# esp32_v2.net
KiCad netlist of a schematic drawn in Altium Designer
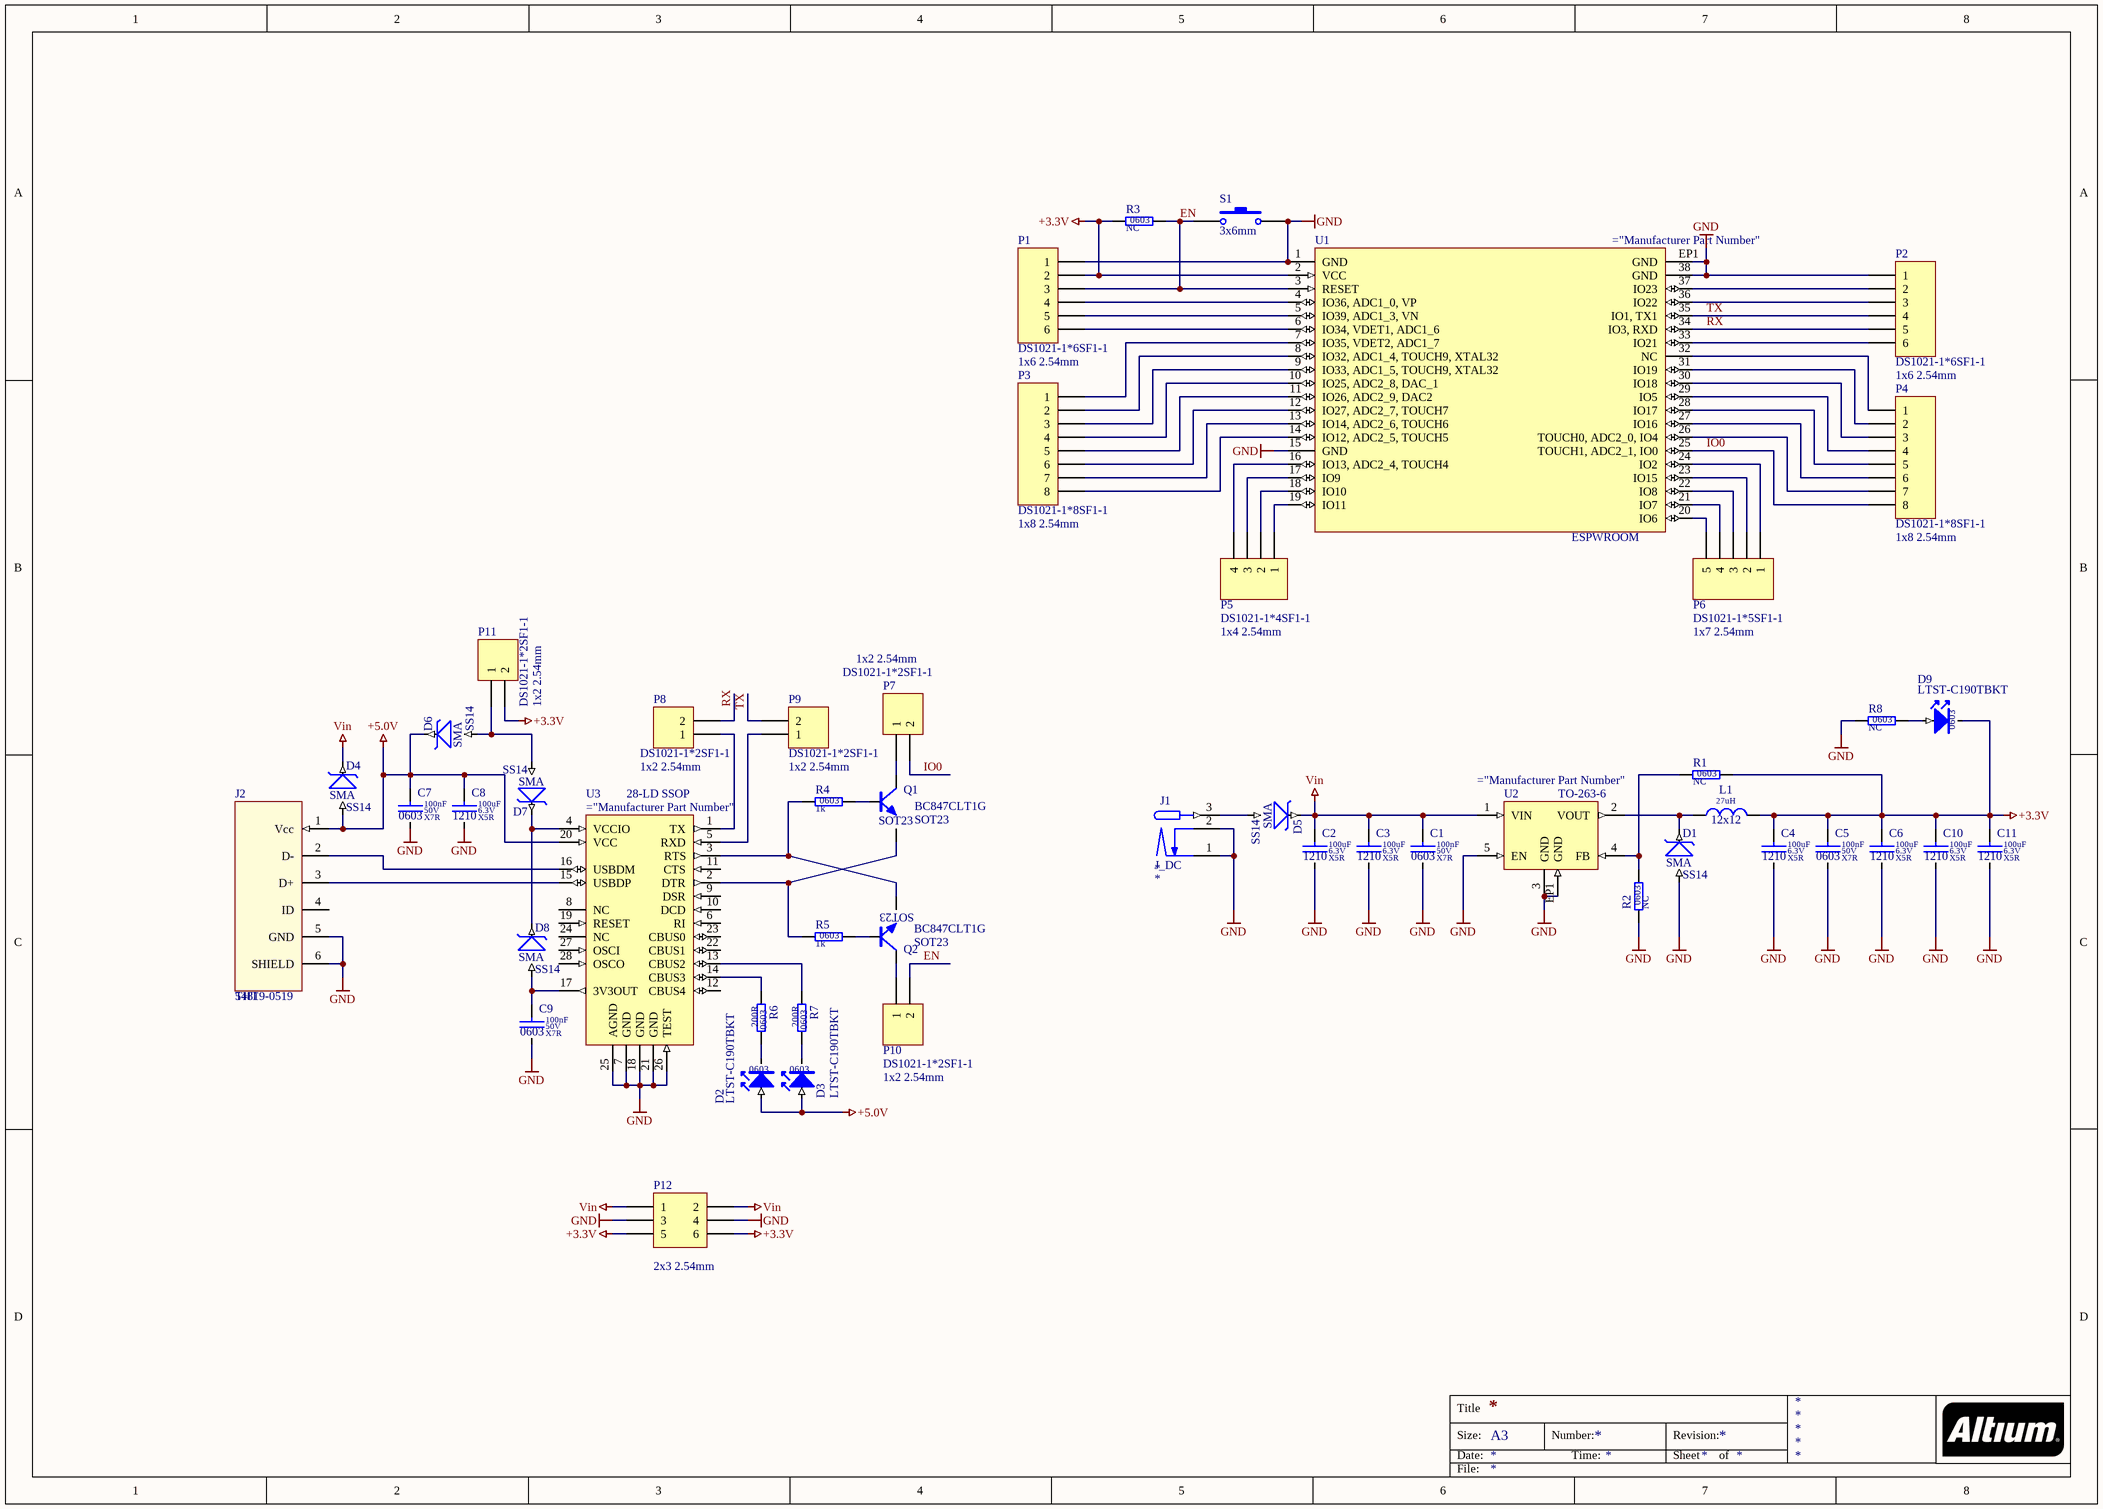
[diagram p0: esp32_v2.SchDoc]

(export (version "E")
  (design (tool "Eeschema 10.0.6"))
  (components
    (comp (ref "C1")
      (value "100nF")
      (footprint "C_0603_1608")
      (description "Capacitor")
      (fields
        (field (name "DIELECTRIC") "X7R")
        (field (name "VOLTAGE") "50V")
        (field (name "SCH_FOOTPRINT") "0603")
        (field (name "PART NUMBER") "C_100nF_50V_X7R_0603_5")
        (field (name "MANUFACTURER") "Samsung")
      )
      (libsource (lib "Library") (part "C"))
    )
    (comp (ref "C2")
      (value "100uF")
      (footprint "C_1210_3225")
      (description "Capacitor")
      (fields
        (field (name "DIELECTRIC") "X5R")
        (field (name "VOLTAGE") "6.3V")
        (field (name "SCH_FOOTPRINT") "1210")
        (field (name "PART NUMBER") "C_100uF_6.3V_X5R_1210_20")
        (field (name "MANUFACTURER") "TDK")
      )
      (libsource (lib "Library") (part "C"))
    )
    (comp (ref "C3")
      (value "100uF")
      (footprint "C_1210_3225")
      (description "Capacitor")
      (fields
        (field (name "DIELECTRIC") "X5R")
        (field (name "VOLTAGE") "6.3V")
        (field (name "SCH_FOOTPRINT") "1210")
        (field (name "PART NUMBER") "C_100uF_6.3V_X5R_1210_20")
        (field (name "MANUFACTURER") "TDK")
      )
      (libsource (lib "Library") (part "C"))
    )
    (comp (ref "C4")
      (value "100uF")
      (footprint "C_1210_3225")
      (description "Capacitor")
      (fields
        (field (name "DIELECTRIC") "X5R")
        (field (name "VOLTAGE") "6.3V")
        (field (name "SCH_FOOTPRINT") "1210")
        (field (name "PART NUMBER") "C_100uF_6.3V_X5R_1210_20")
        (field (name "MANUFACTURER") "TDK")
      )
      (libsource (lib "Library") (part "C"))
    )
    (comp (ref "C5")
      (value "100nF")
      (footprint "C_0603_1608")
      (description "Capacitor")
      (fields
        (field (name "DIELECTRIC") "X7R")
        (field (name "VOLTAGE") "50V")
        (field (name "SCH_FOOTPRINT") "0603")
        (field (name "PART NUMBER") "C_100nF_50V_X7R_0603_5")
        (field (name "MANUFACTURER") "Samsung")
      )
      (libsource (lib "Library") (part "C"))
    )
    (comp (ref "C6")
      (value "100uF")
      (footprint "C_1210_3225")
      (description "Capacitor")
      (fields
        (field (name "DIELECTRIC") "X5R")
        (field (name "VOLTAGE") "6.3V")
        (field (name "SCH_FOOTPRINT") "1210")
        (field (name "PART NUMBER") "C_100uF_6.3V_X5R_1210_20")
        (field (name "MANUFACTURER") "TDK")
      )
      (libsource (lib "Library") (part "C"))
    )
    (comp (ref "C7")
      (value "100nF")
      (footprint "C_0603_1608")
      (description "Capacitor")
      (fields
        (field (name "DIELECTRIC") "X7R")
        (field (name "VOLTAGE") "50V")
        (field (name "SCH_FOOTPRINT") "0603")
        (field (name "PART NUMBER") "C_100nF_50V_X7R_0603_5")
        (field (name "MANUFACTURER") "Samsung")
      )
      (libsource (lib "Library") (part "C"))
    )
    (comp (ref "C8")
      (value "100uF")
      (footprint "C_1210_3225")
      (description "Capacitor")
      (fields
        (field (name "DIELECTRIC") "X5R")
        (field (name "VOLTAGE") "6.3V")
        (field (name "SCH_FOOTPRINT") "1210")
        (field (name "PART NUMBER") "C_100uF_6.3V_X5R_1210_20")
        (field (name "MANUFACTURER") "TDK")
      )
      (libsource (lib "Library") (part "C"))
    )
    (comp (ref "C9")
      (value "100nF")
      (footprint "C_0603_1608")
      (description "Capacitor")
      (fields
        (field (name "DIELECTRIC") "X7R")
        (field (name "VOLTAGE") "50V")
        (field (name "SCH_FOOTPRINT") "0603")
        (field (name "PART NUMBER") "C_100nF_50V_X7R_0603_5")
        (field (name "MANUFACTURER") "Samsung")
      )
      (libsource (lib "Library") (part "C"))
    )
    (comp (ref "C10")
      (value "100uF")
      (footprint "C_1210_3225")
      (description "Capacitor")
      (fields
        (field (name "DIELECTRIC") "X5R")
        (field (name "VOLTAGE") "6.3V")
        (field (name "SCH_FOOTPRINT") "1210")
        (field (name "PART NUMBER") "C_100uF_6.3V_X5R_1210_20")
        (field (name "MANUFACTURER") "TDK")
      )
      (libsource (lib "Library") (part "C"))
    )
    (comp (ref "C11")
      (value "100uF")
      (footprint "C_1210_3225")
      (description "Capacitor")
      (fields
        (field (name "DIELECTRIC") "X5R")
        (field (name "VOLTAGE") "6.3V")
        (field (name "SCH_FOOTPRINT") "1210")
        (field (name "PART NUMBER") "C_100uF_6.3V_X5R_1210_20")
        (field (name "MANUFACTURER") "TDK")
      )
      (libsource (lib "Library") (part "C"))
    )
    (comp (ref "D1")
      (value "SS14")
      (footprint "SMA_DO-214AC")
      (fields
        (field (name "SCH_FOOTPRINT") "SMA")
        (field (name "PART NUMBER") "DS_SS14_1A_40V_SMA")
        (field (name "VOLTAGE") "40V")
        (field (name "MANUFACTURER") "Fairchild Semiconductor")
      )
      (libsource (lib "Library") (part "DS"))
    )
    (comp (ref "D2")
      (value "LTST-C190TBKT")
      (footprint "OL_0603_1608")
      (description "LED_BLUE")
      (fields
        (field (name "SCH_FOOTPRINT") "0603")
        (field (name "PART NUMBER") "OL_B_0603")
        (field (name "MANUFACTURER") "Lite-On")
      )
      (libsource (lib "Library") (part "OL_B"))
    )
    (comp (ref "D3")
      (value "LTST-C190TBKT")
      (footprint "OL_0603_1608")
      (description "LED_BLUE")
      (fields
        (field (name "SCH_FOOTPRINT") "0603")
        (field (name "PART NUMBER") "OL_B_0603")
        (field (name "MANUFACTURER") "Lite-On")
      )
      (libsource (lib "Library") (part "OL_B"))
    )
    (comp (ref "D4")
      (value "SS14")
      (footprint "SMA_DO-214AC")
      (fields
        (field (name "SCH_FOOTPRINT") "SMA")
        (field (name "PART NUMBER") "DS_SS14_1A_40V_SMA")
        (field (name "VOLTAGE") "40V")
        (field (name "MANUFACTURER") "Fairchild Semiconductor")
      )
      (libsource (lib "Library") (part "DS"))
    )
    (comp (ref "D5")
      (value "SS14")
      (footprint "SMA_DO-214AC")
      (fields
        (field (name "SCH_FOOTPRINT") "SMA")
        (field (name "PART NUMBER") "DS_SS14_1A_40V_SMA")
        (field (name "VOLTAGE") "40V")
        (field (name "MANUFACTURER") "Fairchild Semiconductor")
      )
      (libsource (lib "Library") (part "DS"))
    )
    (comp (ref "D6")
      (value "SS14")
      (footprint "SMA_DO-214AC")
      (fields
        (field (name "SCH_FOOTPRINT") "SMA")
        (field (name "PART NUMBER") "DS_SS14_1A_40V_SMA")
        (field (name "VOLTAGE") "40V")
        (field (name "MANUFACTURER") "Fairchild Semiconductor")
      )
      (libsource (lib "Library") (part "DS"))
    )
    (comp (ref "D7")
      (value "SS14")
      (footprint "SMA_DO-214AC")
      (fields
        (field (name "SCH_FOOTPRINT") "SMA")
        (field (name "PART NUMBER") "DS_SS14_1A_40V_SMA")
        (field (name "VOLTAGE") "40V")
        (field (name "MANUFACTURER") "Fairchild Semiconductor")
      )
      (libsource (lib "Library") (part "DS"))
    )
    (comp (ref "D8")
      (value "SS14")
      (footprint "SMA_DO-214AC")
      (fields
        (field (name "SCH_FOOTPRINT") "SMA")
        (field (name "PART NUMBER") "DS_SS14_1A_40V_SMA")
        (field (name "VOLTAGE") "40V")
        (field (name "MANUFACTURER") "Fairchild Semiconductor")
      )
      (libsource (lib "Library") (part "DS"))
    )
    (comp (ref "D9")
      (value "LTST-C190TBKT")
      (footprint "OL_0603_1608")
      (description "LED_BLUE")
      (fields
        (field (name "SCH_FOOTPRINT") "0603")
        (field (name "PART NUMBER") "OL_B_0603")
        (field (name "MANUFACTURER") "Lite-On")
      )
      (libsource (lib "Library") (part "OL_B"))
    )
    (comp (ref "J1")
      (value "J_DC")
      (footprint "DC_5.5")
      (fields
        (field (name "ALTIUM_VALUE") "*")
        (field (name "SCH_FOOTPRINT") "*")
        (field (name "PART NUMBER") "J_DC_5.5mm")
      )
      (libsource (lib "Lib") (part "J_DC"))
    )
    (comp (ref "J2")
      (value "54819-0519")
      (footprint "J_USB_MINIB_54819-0519_THT")
      (description "Złącze USB, Mini USB typu B, USB 2.0 OTG, Montaż przewlekany")
      (fields
        (field (name "PART NUMBER") "J_USB_MINIB_54819-0519")
        (field (name "SCH_FOOTPRINT") "THT")
        (field (name "MANUFACTURER") "Molex")
      )
      (libsource (lib "Library") (part "J_USB_MINIB_54819-0519_THT"))
    )
    (comp (ref "L1")
      (value "27uH")
      (footprint "L_SRR1280-XXXY")
      (description "Induction")
      (fields
        (field (name "SCH_FOOTPRINT") "12x12")
        (field (name "PART NUMBER") "L_27uH_3.9A_SRR1280")
        (field (name "MANUFACTURER") "Bourns")
      )
      (libsource (lib "Library") (part "L"))
    )
    (comp (ref "P1")
      (value "DS1021-1*6SF1-1")
      (footprint "P_HEADER_1x6_2.54")
      (description "Header, 6-Pin")
      (fields
        (field (name "PART NUMBER") "P_HEADER_1x6_2.54")
        (field (name "SCH_FOOTPRINT") "1x6 2.54mm")
        (field (name "MANUFACTURER") "Connfly")
      )
      (libsource (lib "Library") (part "P_HEADER_1x6"))
    )
    (comp (ref "P2")
      (value "DS1021-1*6SF1-1")
      (footprint "P_HEADER_1x6_2.54")
      (description "Header, 6-Pin")
      (fields
        (field (name "PART NUMBER") "P_HEADER_1x6_2.54")
        (field (name "SCH_FOOTPRINT") "1x6 2.54mm")
        (field (name "MANUFACTURER") "Connfly")
      )
      (libsource (lib "") (part "P_HEADER_1x6_1"))
    )
    (comp (ref "P3")
      (value "DS1021-1*8SF1-1")
      (footprint "P_HEADER_1x8_2.54")
      (description "Header, 8-Pin")
      (fields
        (field (name "PART NUMBER") "P_HEADER_1x8_2.54")
        (field (name "SCH_FOOTPRINT") "1x8 2.54mm")
        (field (name "MANUFACTURER") "Connfly")
      )
      (libsource (lib "Library") (part "P_HEADER_1x8"))
    )
    (comp (ref "P4")
      (value "DS1021-1*8SF1-1")
      (footprint "P_HEADER_1x8_2.54")
      (description "Header, 8-Pin")
      (fields
        (field (name "PART NUMBER") "P_HEADER_1x8_2.54")
        (field (name "SCH_FOOTPRINT") "1x8 2.54mm")
        (field (name "MANUFACTURER") "Connfly")
      )
      (libsource (lib "") (part "P_HEADER_1x8_1"))
    )
    (comp (ref "P5")
      (value "DS1021-1*4SF1-1")
      (footprint "P_HEADER_1x4_2.54")
      (description "Header, 4-Pin")
      (fields
        (field (name "PART NUMBER") "P_HEADER_1x4_2.54")
        (field (name "SCH_FOOTPRINT") "1x4 2.54mm")
        (field (name "MANUFACTURER") "Connfly")
      )
      (libsource (lib "Library") (part "P_HEADER_1x4"))
    )
    (comp (ref "P6")
      (value "DS1021-1*5SF1-1")
      (footprint "P_HEADER_1x5_2.54")
      (description "Header, 5-Pin")
      (fields
        (field (name "PART NUMBER") "P_HEADER_1x5_2.54")
        (field (name "SCH_FOOTPRINT") "1x7 2.54mm")
        (field (name "MANUFACTURER") "Connfly")
      )
      (libsource (lib "Library") (part "P_HEADER_1x5"))
    )
    (comp (ref "P7")
      (value "DS1021-1*2SF1-1")
      (footprint "P_HEADER_1x2_2.54")
      (description "Header, 2-Pin")
      (fields
        (field (name "PART NUMBER") "P_HEADER_1x2_2.54")
        (field (name "SCH_FOOTPRINT") "1x2 2.54mm")
        (field (name "MANUFACTURER") "Connfly")
      )
      (libsource (lib "") (part "P_HEADER_1x2_1"))
    )
    (comp (ref "P8")
      (value "DS1021-1*2SF1-1")
      (footprint "P_HEADER_1x2_2.54")
      (description "Header, 2-Pin")
      (fields
        (field (name "PART NUMBER") "P_HEADER_1x2_2.54")
        (field (name "SCH_FOOTPRINT") "1x2 2.54mm")
        (field (name "MANUFACTURER") "Connfly")
      )
      (libsource (lib "Library") (part "P_HEADER_1x2"))
    )
    (comp (ref "P9")
      (value "DS1021-1*2SF1-1")
      (footprint "P_HEADER_1x2_2.54")
      (description "Header, 2-Pin")
      (fields
        (field (name "PART NUMBER") "P_HEADER_1x2_2.54")
        (field (name "SCH_FOOTPRINT") "1x2 2.54mm")
        (field (name "MANUFACTURER") "Connfly")
      )
      (libsource (lib "") (part "P_HEADER_1x2_1"))
    )
    (comp (ref "P10")
      (value "DS1021-1*2SF1-1")
      (footprint "P_HEADER_1x2_2.54")
      (description "Header, 2-Pin")
      (fields
        (field (name "PART NUMBER") "P_HEADER_1x2_2.54")
        (field (name "SCH_FOOTPRINT") "1x2 2.54mm")
        (field (name "MANUFACTURER") "Connfly")
      )
      (libsource (lib "Library") (part "P_HEADER_1x2"))
    )
    (comp (ref "P11")
      (value "DS1021-1*2SF1-1")
      (footprint "P_HEADER_1x2_2.54")
      (description "Header, 2-Pin")
      (fields
        (field (name "PART NUMBER") "P_HEADER_1x2_2.54")
        (field (name "SCH_FOOTPRINT") "1x2 2.54mm")
        (field (name "MANUFACTURER") "Connfly")
      )
      (libsource (lib "") (part "P_HEADER_1x2_1"))
    )
    (comp (ref "P12")
      (value "Goldpin")
      (footprint "P_HEADER_2x3_2.54")
      (description "Header, 3-Pin, Dual row")
      (fields (field (name "PART NUMBER") "P_HEADER_2x3_2.54") (field (name "SCH_FOOTPRINT") "2x3 2.54mm"))
      (libsource (lib "Library") (part "P_HEADER_2x3"))
    )
    (comp (ref "Q1")
      (value "BC847CLT1G")
      (footprint "SOT23_TO236_SC59")
      (fields
        (field (name "PART NUMBER") "QNP_BC847C_45V_0A1")
        (field (name "SCH_FOOTPRINT") "SOT23")
        (field (name "VOLTAGE") "45V")
        (field (name "MANUFACTURER") "ON Semiconductor")
      )
      (libsource (lib "Library") (part "QNP_BEC"))
    )
    (comp (ref "Q2")
      (value "BC847CLT1G")
      (footprint "SOT23_TO236_SC59")
      (fields
        (field (name "PART NUMBER") "QNP_BC847C_45V_0A1")
        (field (name "SCH_FOOTPRINT") "SOT23")
        (field (name "VOLTAGE") "45V")
        (field (name "MANUFACTURER") "ON Semiconductor")
      )
      (libsource (lib "Library") (part "QNP_BEC"))
    )
    (comp (ref "R1")
      (value "NC")
      (footprint "R_NC_0603_1608")
      (fields
        (field (name "SCH_FOOTPRINT") "0603")
        (field (name "PART NUMBER") "R_GENERIC_0603")
        (field (name "Comment") "Resistor")
      )
      (libsource (lib "Library") (part "R"))
    )
    (comp (ref "R2")
      (value "NC")
      (footprint "R_NC_0603_1608")
      (fields
        (field (name "SCH_FOOTPRINT") "0603")
        (field (name "PART NUMBER") "R_GENERIC_0603")
        (field (name "Comment") "Resistor")
      )
      (libsource (lib "Library") (part "R"))
    )
    (comp (ref "R3")
      (value "NC")
      (footprint "R_NC_0603_1608")
      (fields
        (field (name "SCH_FOOTPRINT") "0603")
        (field (name "PART NUMBER") "R_GENERIC_0603")
        (field (name "Comment") "Resistor")
      )
      (libsource (lib "Library") (part "R"))
    )
    (comp (ref "R4")
      (value "1k")
      (footprint "R_0603_1608")
      (fields
        (field (name "SCH_FOOTPRINT") "0603")
        (field (name "PART NUMBER") "R_1k_0603_1")
        (field (name "VOLTAGE") "75V")
        (field (name "POWER") "100mW")
      )
      (libsource (lib "Library") (part "R"))
    )
    (comp (ref "R5")
      (value "1k")
      (footprint "R_0603_1608")
      (fields
        (field (name "SCH_FOOTPRINT") "0603")
        (field (name "PART NUMBER") "R_1k_0603_1")
        (field (name "VOLTAGE") "75V")
        (field (name "POWER") "100mW")
      )
      (libsource (lib "Library") (part "R"))
    )
    (comp (ref "R6")
      (value "200R")
      (footprint "R_0603_1608")
      (fields
        (field (name "SCH_FOOTPRINT") "0603")
        (field (name "PART NUMBER") "R_200R_0603_1")
        (field (name "VOLTAGE") "50V")
        (field (name "POWER") "100mW")
      )
      (libsource (lib "Library") (part "R"))
    )
    (comp (ref "R7")
      (value "200R")
      (footprint "R_0603_1608")
      (fields
        (field (name "SCH_FOOTPRINT") "0603")
        (field (name "PART NUMBER") "R_200R_0603_1")
        (field (name "VOLTAGE") "50V")
        (field (name "POWER") "100mW")
      )
      (libsource (lib "Library") (part "R"))
    )
    (comp (ref "R8")
      (value "NC")
      (footprint "R_NC_0603_1608")
      (fields
        (field (name "SCH_FOOTPRINT") "0603")
        (field (name "PART NUMBER") "R_GENERIC_0603")
        (field (name "Comment") "Resistor")
      )
      (libsource (lib "Library") (part "R"))
    )
    (comp (ref "S1")
      (value "3x6mm")
      (footprint "S_TACTSWITCH3x6")
      (description "Tact Switch")
      (fields
        (field (name "PART NUMBER") "S_TACTSWITCH")
        (field (name "SCH_FOOTPRINT") "3x6mm")
        (field (name "MANUFACTURER") "Ninigi")
      )
      (libsource (lib "Library") (part "S_TACTSWITCH"))
    )
    (comp (ref "U1")
      (value "U_ESP32")
      (footprint "ESP_WROOM_32")
      (fields (field (name "SCH_FOOTPRINT") "ESPWROOM") (field (name "PART NUMBER") "M_ESP32_WROOM"))
      (libsource (lib "Lib") (part "U_ESP32"))
    )
    (comp (ref "U2")
      (value "VR_LM2596")
      (footprint "TO-263-6")
      (fields (field (name "SCH_FOOTPRINT") "TO-263-6") (field (name "PART NUMBER") "VR_LM2596-ADJ"))
      (libsource (lib "Lib") (part "VR_LM2596"))
    )
    (comp (ref "U3")
      (value "U_FT232RL")
      (footprint "SSOP28_5X10X17")
      (fields (field (name "SCH_FOOTPRINT") "28-LD SSOP") (field (name "PART NUMBER") "U_FT232RLR"))
      (libsource (lib "Lib") (part "U_FT232RL"))
    )
  )
  (nets
    (net (code "1") (name "+3.3V") (class "Default")
      (node (ref "C10") (pin "1") (pinfunction "1_1") (pintype "passive"))
      (node (ref "C11") (pin "1") (pinfunction "1_1") (pintype "passive"))
      (node (ref "C4") (pin "1") (pinfunction "1_1") (pintype "passive"))
      (node (ref "C5") (pin "1") (pinfunction "1_1") (pintype "passive"))
      (node (ref "C6") (pin "1") (pinfunction "1_1") (pintype "passive"))
      (node (ref "D9") (pin "1") (pinfunction "K_1") (pintype "output"))
      (node (ref "L1") (pin "2") (pinfunction "2_2") (pintype "passive"))
      (node (ref "P1") (pin "2") (pinfunction "2_2") (pintype "passive"))
      (node (ref "P11") (pin "2") (pinfunction "2_2") (pintype "passive"))
      (node (ref "P12") (pin "5") (pinfunction "5_5") (pintype "passive"))
      (node (ref "P12") (pin "6") (pinfunction "6_6") (pintype "passive"))
      (node (ref "R1") (pin "2") (pinfunction "2_2") (pintype "passive"))
      (node (ref "R3") (pin "1") (pinfunction "1_1") (pintype "passive"))
      (node (ref "U1") (pin "2") (pinfunction "VCC_2") (pintype "input"))
    )
    (net (code "2") (name "+5.0V") (class "Default")
      (node (ref "C7") (pin "1") (pinfunction "1_1") (pintype "passive"))
      (node (ref "C8") (pin "1") (pinfunction "1_1") (pintype "passive"))
      (node (ref "D2") (pin "2") (pinfunction "A_2") (pintype "input"))
      (node (ref "D3") (pin "2") (pinfunction "A_2") (pintype "input"))
      (node (ref "D4") (pin "2") (pintype "input"))
      (node (ref "D6") (pin "1") (pintype "output"))
      (node (ref "J2") (pin "1") (pinfunction "Vcc_1") (pintype "input"))
      (node (ref "U3") (pin "20") (pinfunction "VCC_20") (pintype "input"))
    )
    (net (code "3") (name "/EN") (class "Default")
      (node (ref "P1") (pin "3") (pinfunction "3_3") (pintype "passive"))
      (node (ref "P10") (pin "2") (pinfunction "2_2") (pintype "passive"))
      (node (ref "R3") (pin "2") (pinfunction "2_2") (pintype "passive"))
      (node (ref "S1") (pin "1") (pinfunction "1_1") (pintype "passive"))
      (node (ref "U1") (pin "3") (pinfunction "RESET_3") (pintype "input"))
    )
    (net (code "4") (name "/IO0") (class "Default")
      (node (ref "P4") (pin "8") (pinfunction "8_8") (pintype "passive"))
      (node (ref "P7") (pin "2") (pinfunction "2_2") (pintype "passive"))
      (node (ref "U1") (pin "25") (pinfunction "TOUCH1,_ADC2_1,_IO0_25") (pintype "bidirectional"))
    )
    (net (code "5") (name "/RX") (class "Default")
      (node (ref "P2") (pin "5") (pinfunction "5_5") (pintype "passive"))
      (node (ref "P8") (pin "2") (pinfunction "2_2") (pintype "passive"))
      (node (ref "U1") (pin "34") (pinfunction "IO3,_RXD_34") (pintype "bidirectional"))
    )
    (net (code "6") (name "/TX") (class "Default")
      (node (ref "P2") (pin "4") (pinfunction "4_4") (pintype "passive"))
      (node (ref "P9") (pin "2") (pinfunction "2_2") (pintype "passive"))
      (node (ref "U1") (pin "35") (pinfunction "IO1,_TX1_35") (pintype "bidirectional"))
    )
    (net (code "7") (name "GND") (class "Default")
      (node (ref "C1") (pin "2") (pinfunction "2_2") (pintype "passive"))
      (node (ref "C10") (pin "2") (pinfunction "2_2") (pintype "passive"))
      (node (ref "C11") (pin "2") (pinfunction "2_2") (pintype "passive"))
      (node (ref "C2") (pin "2") (pinfunction "2_2") (pintype "passive"))
      (node (ref "C3") (pin "2") (pinfunction "2_2") (pintype "passive"))
      (node (ref "C4") (pin "2") (pinfunction "2_2") (pintype "passive"))
      (node (ref "C5") (pin "2") (pinfunction "2_2") (pintype "passive"))
      (node (ref "C6") (pin "2") (pinfunction "2_2") (pintype "passive"))
      (node (ref "C7") (pin "2") (pinfunction "2_2") (pintype "passive"))
      (node (ref "C8") (pin "2") (pinfunction "2_2") (pintype "passive"))
      (node (ref "C9") (pin "2") (pinfunction "2_2") (pintype "passive"))
      (node (ref "D1") (pin "2") (pintype "input"))
      (node (ref "J1") (pin "1") (pinfunction "1_1") (pintype "power_in"))
      (node (ref "J1") (pin "2") (pinfunction "2_2") (pintype "passive"))
      (node (ref "J2") (pin "5") (pinfunction "GND_5") (pintype "power_in"))
      (node (ref "J2") (pin "6") (pinfunction "SHIELD_6") (pintype "passive"))
      (node (ref "P1") (pin "1") (pinfunction "1_1") (pintype "passive"))
      (node (ref "P12") (pin "3") (pinfunction "3_3") (pintype "passive"))
      (node (ref "P12") (pin "4") (pinfunction "4_4") (pintype "passive"))
      (node (ref "P2") (pin "1") (pinfunction "1_1") (pintype "passive"))
      (node (ref "R2") (pin "1") (pinfunction "1_1") (pintype "passive"))
      (node (ref "R8") (pin "1") (pinfunction "1_1") (pintype "passive"))
      (node (ref "S1") (pin "2") (pinfunction "2_2") (pintype "passive"))
      (node (ref "U1") (pin "1") (pinfunction "GND_1") (pintype "power_in"))
      (node (ref "U1") (pin "15") (pinfunction "GND_15") (pintype "power_in"))
      (node (ref "U1") (pin "38") (pinfunction "GND_38") (pintype "power_in"))
      (node (ref "U1") (pin "EP1") (pinfunction "GND_EP1") (pintype "power_in"))
      (node (ref "U2") (pin "3") (pinfunction "GND_3") (pintype "power_in"))
      (node (ref "U2") (pin "5") (pinfunction "EN_5") (pintype "input"))
      (node (ref "U2") (pin "EP1") (pinfunction "GND_EP1") (pintype "input"))
      (node (ref "U3") (pin "18") (pinfunction "GND_18") (pintype "power_in"))
      (node (ref "U3") (pin "21") (pinfunction "GND_21") (pintype "power_in"))
      (node (ref "U3") (pin "25") (pinfunction "AGND_25") (pintype "power_in"))
      (node (ref "U3") (pin "26") (pinfunction "TEST_26") (pintype "input"))
      (node (ref "U3") (pin "7") (pinfunction "GND_7") (pintype "power_in"))
    )
    (net (code "8") (name "Net-(D2-K)") (class "Default")
      (node (ref "D2") (pin "1") (pinfunction "K_1") (pintype "output"))
      (node (ref "R6") (pin "2") (pinfunction "2_2") (pintype "passive"))
    )
    (net (code "9") (name "Net-(D3-K)") (class "Default")
      (node (ref "D3") (pin "1") (pinfunction "K_1") (pintype "output"))
      (node (ref "R7") (pin "2") (pinfunction "2_2") (pintype "passive"))
    )
    (net (code "10") (name "Net-(D5-Pad2)") (class "Default")
      (node (ref "D5") (pin "2") (pintype "input"))
      (node (ref "J1") (pin "3") (pinfunction "3_3") (pintype "output"))
    )
    (net (code "11") (name "Net-(D6-Pad2)") (class "Default")
      (node (ref "D6") (pin "2") (pintype "input"))
      (node (ref "D7") (pin "2") (pintype "input"))
      (node (ref "P11") (pin "1") (pinfunction "1_1") (pintype "passive"))
    )
    (net (code "12") (name "Net-(D9-A)") (class "Default")
      (node (ref "D9") (pin "2") (pinfunction "A_2") (pintype "input"))
      (node (ref "R8") (pin "2") (pinfunction "2_2") (pintype "passive"))
    )
    (net (code "13") (name "Net-(J2-D+)") (class "Default")
      (node (ref "J2") (pin "3") (pinfunction "D+_3") (pintype "passive"))
      (node (ref "U3") (pin "15") (pinfunction "USBDP_15") (pintype "bidirectional"))
    )
    (net (code "14") (name "Net-(J2-D-)") (class "Default")
      (node (ref "J2") (pin "2") (pinfunction "D-_2") (pintype "passive"))
      (node (ref "U3") (pin "16") (pinfunction "USBDM_16") (pintype "bidirectional"))
    )
    (net (code "15") (name "Net-(Q1-B)") (class "Default")
      (node (ref "Q1") (pin "1") (pinfunction "B_1") (pintype "passive"))
      (node (ref "R4") (pin "2") (pinfunction "2_2") (pintype "passive"))
    )
    (net (code "16") (name "Net-(Q1-C)") (class "Default")
      (node (ref "P7") (pin "1") (pinfunction "1_1") (pintype "passive"))
      (node (ref "Q1") (pin "3") (pinfunction "C_3") (pintype "passive"))
    )
    (net (code "17") (name "Net-(Q1-E)") (class "Default")
      (node (ref "Q1") (pin "2") (pinfunction "E_2") (pintype "passive"))
      (node (ref "R5") (pin "1") (pinfunction "1_1") (pintype "passive"))
      (node (ref "U3") (pin "2") (pinfunction "DTR_2") (pintype "output"))
    )
    (net (code "18") (name "Net-(Q2-B)") (class "Default")
      (node (ref "Q2") (pin "1") (pinfunction "B_1") (pintype "passive"))
      (node (ref "R5") (pin "2") (pinfunction "2_2") (pintype "passive"))
    )
    (net (code "19") (name "Net-(Q2-C)") (class "Default")
      (node (ref "P10") (pin "1") (pinfunction "1_1") (pintype "passive"))
      (node (ref "Q2") (pin "3") (pinfunction "C_3") (pintype "passive"))
    )
    (net (code "20") (name "Net-(Q2-E)") (class "Default")
      (node (ref "Q2") (pin "2") (pinfunction "E_2") (pintype "passive"))
      (node (ref "R4") (pin "1") (pinfunction "1_1") (pintype "passive"))
      (node (ref "U3") (pin "3") (pinfunction "RTS_3") (pintype "output"))
    )
    (net (code "21") (name "Net-(U1-IO2)") (class "Default")
      (node (ref "P6") (pin "1") (pinfunction "1_1") (pintype "passive"))
      (node (ref "U1") (pin "24") (pinfunction "IO2_24") (pintype "bidirectional"))
    )
    (net (code "22") (name "Net-(U1-IO5)") (class "Default")
      (node (ref "P4") (pin "4") (pinfunction "4_4") (pintype "passive"))
      (node (ref "U1") (pin "29") (pinfunction "IO5_29") (pintype "bidirectional"))
    )
    (net (code "23") (name "Net-(U1-IO6)") (class "Default")
      (node (ref "P6") (pin "5") (pinfunction "5_5") (pintype "passive"))
      (node (ref "U1") (pin "20") (pinfunction "IO6_20") (pintype "bidirectional"))
    )
    (net (code "24") (name "Net-(U1-IO7)") (class "Default")
      (node (ref "P6") (pin "4") (pinfunction "4_4") (pintype "passive"))
      (node (ref "U1") (pin "21") (pinfunction "IO7_21") (pintype "bidirectional"))
    )
    (net (code "25") (name "Net-(U1-IO8)") (class "Default")
      (node (ref "P6") (pin "3") (pinfunction "3_3") (pintype "passive"))
      (node (ref "U1") (pin "22") (pinfunction "IO8_22") (pintype "bidirectional"))
    )
    (net (code "26") (name "Net-(U1-IO9)") (class "Default")
      (node (ref "P5") (pin "3") (pinfunction "3_3") (pintype "passive"))
      (node (ref "U1") (pin "17") (pinfunction "IO9_17") (pintype "bidirectional"))
    )
    (net (code "27") (name "Net-(U1-IO10)") (class "Default")
      (node (ref "P5") (pin "2") (pinfunction "2_2") (pintype "passive"))
      (node (ref "U1") (pin "18") (pinfunction "IO10_18") (pintype "bidirectional"))
    )
    (net (code "28") (name "Net-(U1-IO11)") (class "Default")
      (node (ref "P5") (pin "1") (pinfunction "1_1") (pintype "passive"))
      (node (ref "U1") (pin "19") (pinfunction "IO11_19") (pintype "bidirectional"))
    )
    (net (code "29") (name "Net-(U1-IO12,_ADC2_5,_TOUCH5)") (class "Default")
      (node (ref "P3") (pin "8") (pinfunction "8_8") (pintype "passive"))
      (node (ref "U1") (pin "14") (pinfunction "IO12,_ADC2_5,_TOUCH5_14") (pintype "bidirectional"))
    )
    (net (code "30") (name "Net-(U1-IO13,_ADC2_4,_TOUCH4)") (class "Default")
      (node (ref "P5") (pin "4") (pinfunction "4_4") (pintype "passive"))
      (node (ref "U1") (pin "16") (pinfunction "IO13,_ADC2_4,_TOUCH4_16") (pintype "bidirectional"))
    )
    (net (code "31") (name "Net-(U1-IO14,_ADC2_6,_TOUCH6)") (class "Default")
      (node (ref "P3") (pin "7") (pinfunction "7_7") (pintype "passive"))
      (node (ref "U1") (pin "13") (pinfunction "IO14,_ADC2_6,_TOUCH6_13") (pintype "bidirectional"))
    )
    (net (code "32") (name "Net-(U1-IO15)") (class "Default")
      (node (ref "P6") (pin "2") (pinfunction "2_2") (pintype "passive"))
      (node (ref "U1") (pin "23") (pinfunction "IO15_23") (pintype "bidirectional"))
    )
    (net (code "33") (name "Net-(U1-IO16)") (class "Default")
      (node (ref "P4") (pin "6") (pinfunction "6_6") (pintype "passive"))
      (node (ref "U1") (pin "27") (pinfunction "IO16_27") (pintype "bidirectional"))
    )
    (net (code "34") (name "Net-(U1-IO17)") (class "Default")
      (node (ref "P4") (pin "5") (pinfunction "5_5") (pintype "passive"))
      (node (ref "U1") (pin "28") (pinfunction "IO17_28") (pintype "bidirectional"))
    )
    (net (code "35") (name "Net-(U1-IO18)") (class "Default")
      (node (ref "P4") (pin "3") (pinfunction "3_3") (pintype "passive"))
      (node (ref "U1") (pin "30") (pinfunction "IO18_30") (pintype "bidirectional"))
    )
    (net (code "36") (name "Net-(U1-IO19)") (class "Default")
      (node (ref "P4") (pin "2") (pinfunction "2_2") (pintype "passive"))
      (node (ref "U1") (pin "31") (pinfunction "IO19_31") (pintype "bidirectional"))
    )
    (net (code "37") (name "Net-(U1-IO21)") (class "Default")
      (node (ref "P2") (pin "6") (pinfunction "6_6") (pintype "passive"))
      (node (ref "U1") (pin "33") (pinfunction "IO21_33") (pintype "bidirectional"))
    )
    (net (code "38") (name "Net-(U1-IO22)") (class "Default")
      (node (ref "P2") (pin "3") (pinfunction "3_3") (pintype "passive"))
      (node (ref "U1") (pin "36") (pinfunction "IO22_36") (pintype "bidirectional"))
    )
    (net (code "39") (name "Net-(U1-IO23)") (class "Default")
      (node (ref "P2") (pin "2") (pinfunction "2_2") (pintype "passive"))
      (node (ref "U1") (pin "37") (pinfunction "IO23_37") (pintype "bidirectional"))
    )
    (net (code "40") (name "Net-(U1-IO25,_ADC2_8,_DAC_1)") (class "Default")
      (node (ref "P3") (pin "4") (pinfunction "4_4") (pintype "passive"))
      (node (ref "U1") (pin "10") (pinfunction "IO25,_ADC2_8,_DAC_1_10") (pintype "bidirectional"))
    )
    (net (code "41") (name "Net-(U1-IO26,_ADC2_9,_DAC2)") (class "Default")
      (node (ref "P3") (pin "5") (pinfunction "5_5") (pintype "passive"))
      (node (ref "U1") (pin "11") (pinfunction "IO26,_ADC2_9,_DAC2_11") (pintype "bidirectional"))
    )
    (net (code "42") (name "Net-(U1-IO27,_ADC2_7,_TOUCH7)") (class "Default")
      (node (ref "P3") (pin "6") (pinfunction "6_6") (pintype "passive"))
      (node (ref "U1") (pin "12") (pinfunction "IO27,_ADC2_7,_TOUCH7_12") (pintype "bidirectional"))
    )
    (net (code "43") (name "Net-(U1-IO32,_ADC1_4,_TOUCH9,_XTAL32)") (class "Default")
      (node (ref "P3") (pin "2") (pinfunction "2_2") (pintype "passive"))
      (node (ref "U1") (pin "8") (pinfunction "IO32,_ADC1_4,_TOUCH9,_XTAL32_8") (pintype "bidirectional"))
    )
    (net (code "44") (name "Net-(U1-IO33,_ADC1_5,_TOUCH9,_XTAL32)") (class "Default")
      (node (ref "P3") (pin "3") (pinfunction "3_3") (pintype "passive"))
      (node (ref "U1") (pin "9") (pinfunction "IO33,_ADC1_5,_TOUCH9,_XTAL32_9") (pintype "bidirectional"))
    )
    (net (code "45") (name "Net-(U1-IO34,_VDET1,_ADC1_6)") (class "Default")
      (node (ref "P1") (pin "6") (pinfunction "6_6") (pintype "passive"))
      (node (ref "U1") (pin "6") (pinfunction "IO34,_VDET1,_ADC1_6_6") (pintype "bidirectional"))
    )
    (net (code "46") (name "Net-(U1-IO35,_VDET2,_ADC1_7)") (class "Default")
      (node (ref "P3") (pin "1") (pinfunction "1_1") (pintype "passive"))
      (node (ref "U1") (pin "7") (pinfunction "IO35,_VDET2,_ADC1_7_7") (pintype "bidirectional"))
    )
    (net (code "47") (name "Net-(U1-IO36,_ADC1_0,_VP)") (class "Default")
      (node (ref "P1") (pin "4") (pinfunction "4_4") (pintype "passive"))
      (node (ref "U1") (pin "4") (pinfunction "IO36,_ADC1_0,_VP_4") (pintype "bidirectional"))
    )
    (net (code "48") (name "Net-(U1-IO39,_ADC1_3,_VN)") (class "Default")
      (node (ref "P1") (pin "5") (pinfunction "5_5") (pintype "passive"))
      (node (ref "U1") (pin "5") (pinfunction "IO39,_ADC1_3,_VN_5") (pintype "bidirectional"))
    )
    (net (code "49") (name "Net-(U1-NC)") (class "Default")
      (node (ref "P4") (pin "1") (pinfunction "1_1") (pintype "passive"))
      (node (ref "U1") (pin "32") (pinfunction "NC_32") (pintype "passive"))
    )
    (net (code "50") (name "Net-(U1-TOUCH0,_ADC2_0,_IO4)") (class "Default")
      (node (ref "P4") (pin "7") (pinfunction "7_7") (pintype "passive"))
      (node (ref "U1") (pin "26") (pinfunction "TOUCH0,_ADC2_0,_IO4_26") (pintype "bidirectional"))
    )
    (net (code "51") (name "Net-(U2-FB)") (class "Default")
      (node (ref "R1") (pin "1") (pinfunction "1_1") (pintype "passive"))
      (node (ref "R2") (pin "2") (pinfunction "2_2") (pintype "passive"))
      (node (ref "U2") (pin "4") (pinfunction "FB_4") (pintype "input"))
    )
    (net (code "52") (name "Net-(U2-VOUT)") (class "Default")
      (node (ref "D1") (pin "1") (pintype "output"))
      (node (ref "L1") (pin "1") (pinfunction "1_1") (pintype "passive"))
      (node (ref "U2") (pin "2") (pinfunction "VOUT_2") (pintype "output"))
    )
    (net (code "53") (name "Net-(U3-3V3OUT)") (class "Default")
      (node (ref "C9") (pin "1") (pinfunction "1_1") (pintype "passive"))
      (node (ref "D8") (pin "2") (pintype "input"))
      (node (ref "U3") (pin "17") (pinfunction "3V3OUT_17") (pintype "output"))
    )
    (net (code "54") (name "Net-(U3-CBUS2)") (class "Default")
      (node (ref "R7") (pin "1") (pinfunction "1_1") (pintype "passive"))
      (node (ref "U3") (pin "13") (pinfunction "CBUS2_13") (pintype "bidirectional"))
    )
    (net (code "55") (name "Net-(U3-CBUS3)") (class "Default")
      (node (ref "R6") (pin "1") (pinfunction "1_1") (pintype "passive"))
      (node (ref "U3") (pin "14") (pinfunction "CBUS3_14") (pintype "bidirectional"))
    )
    (net (code "56") (name "Net-(U3-RXD)") (class "Default")
      (node (ref "P9") (pin "1") (pinfunction "1_1") (pintype "passive"))
      (node (ref "U3") (pin "5") (pinfunction "RXD_5") (pintype "input"))
    )
    (net (code "57") (name "Net-(U3-TX)") (class "Default")
      (node (ref "P8") (pin "1") (pinfunction "1_1") (pintype "passive"))
      (node (ref "U3") (pin "1") (pinfunction "TX_1") (pintype "output"))
    )
    (net (code "58") (name "Net-(U3-VCCIO)") (class "Default")
      (node (ref "D7") (pin "1") (pintype "output"))
      (node (ref "D8") (pin "1") (pintype "output"))
      (node (ref "U3") (pin "4") (pinfunction "VCCIO_4") (pintype "input"))
    )
    (net (code "59") (name "Vin") (class "Default")
      (node (ref "C1") (pin "1") (pinfunction "1_1") (pintype "passive"))
      (node (ref "C2") (pin "1") (pinfunction "1_1") (pintype "passive"))
      (node (ref "C3") (pin "1") (pinfunction "1_1") (pintype "passive"))
      (node (ref "D4") (pin "1") (pintype "output"))
      (node (ref "D5") (pin "1") (pintype "output"))
      (node (ref "P12") (pin "1") (pinfunction "1_1") (pintype "passive"))
      (node (ref "P12") (pin "2") (pinfunction "2_2") (pintype "passive"))
      (node (ref "U2") (pin "1") (pinfunction "VIN_1") (pintype "input"))
    )
    (net (code "60") (name "unconnected-(J2-ID-Pad4)") (class "Default")
      (node (ref "J2") (pin "4") (pinfunction "ID_4") (pintype "passive"))
    )
    (net (code "61") (name "unconnected-(U3-CBUS0-Pad23)") (class "Default")
      (node (ref "U3") (pin "23") (pinfunction "CBUS0_23") (pintype "bidirectional"))
    )
    (net (code "62") (name "unconnected-(U3-CBUS1-Pad22)") (class "Default")
      (node (ref "U3") (pin "22") (pinfunction "CBUS1_22") (pintype "bidirectional"))
    )
    (net (code "63") (name "unconnected-(U3-CBUS4-Pad12)") (class "Default")
      (node (ref "U3") (pin "12") (pinfunction "CBUS4_12") (pintype "bidirectional"))
    )
    (net (code "64") (name "unconnected-(U3-CTS-Pad11)") (class "Default")
      (node (ref "U3") (pin "11") (pinfunction "CTS_11") (pintype "input"))
    )
    (net (code "65") (name "unconnected-(U3-DCD-Pad10)") (class "Default")
      (node (ref "U3") (pin "10") (pinfunction "DCD_10") (pintype "input"))
    )
    (net (code "66") (name "unconnected-(U3-DSR-Pad9)") (class "Default")
      (node (ref "U3") (pin "9") (pinfunction "DSR_9") (pintype "input"))
    )
    (net (code "67") (name "unconnected-(U3-NC-Pad8)") (class "Default")
      (node (ref "U3") (pin "8") (pinfunction "NC_8") (pintype "passive"))
    )
    (net (code "68") (name "unconnected-(U3-NC-Pad24)") (class "Default")
      (node (ref "U3") (pin "24") (pinfunction "NC_24") (pintype "passive"))
    )
    (net (code "69") (name "unconnected-(U3-OSCI-Pad27)") (class "Default")
      (node (ref "U3") (pin "27") (pinfunction "OSCI_27") (pintype "input"))
    )
    (net (code "70") (name "unconnected-(U3-OSCO-Pad28)") (class "Default")
      (node (ref "U3") (pin "28") (pinfunction "OSCO_28") (pintype "input"))
    )
    (net (code "71") (name "unconnected-(U3-RESET-Pad19)") (class "Default")
      (node (ref "U3") (pin "19") (pinfunction "RESET_19") (pintype "input"))
    )
    (net (code "72") (name "unconnected-(U3-RI-Pad6)") (class "Default")
      (node (ref "U3") (pin "6") (pinfunction "RI_6") (pintype "input"))
    )
  )
)
